# Acondicionamiento_de_la_se_al.net
KiCad netlist of a schematic drawn in Altium Designer
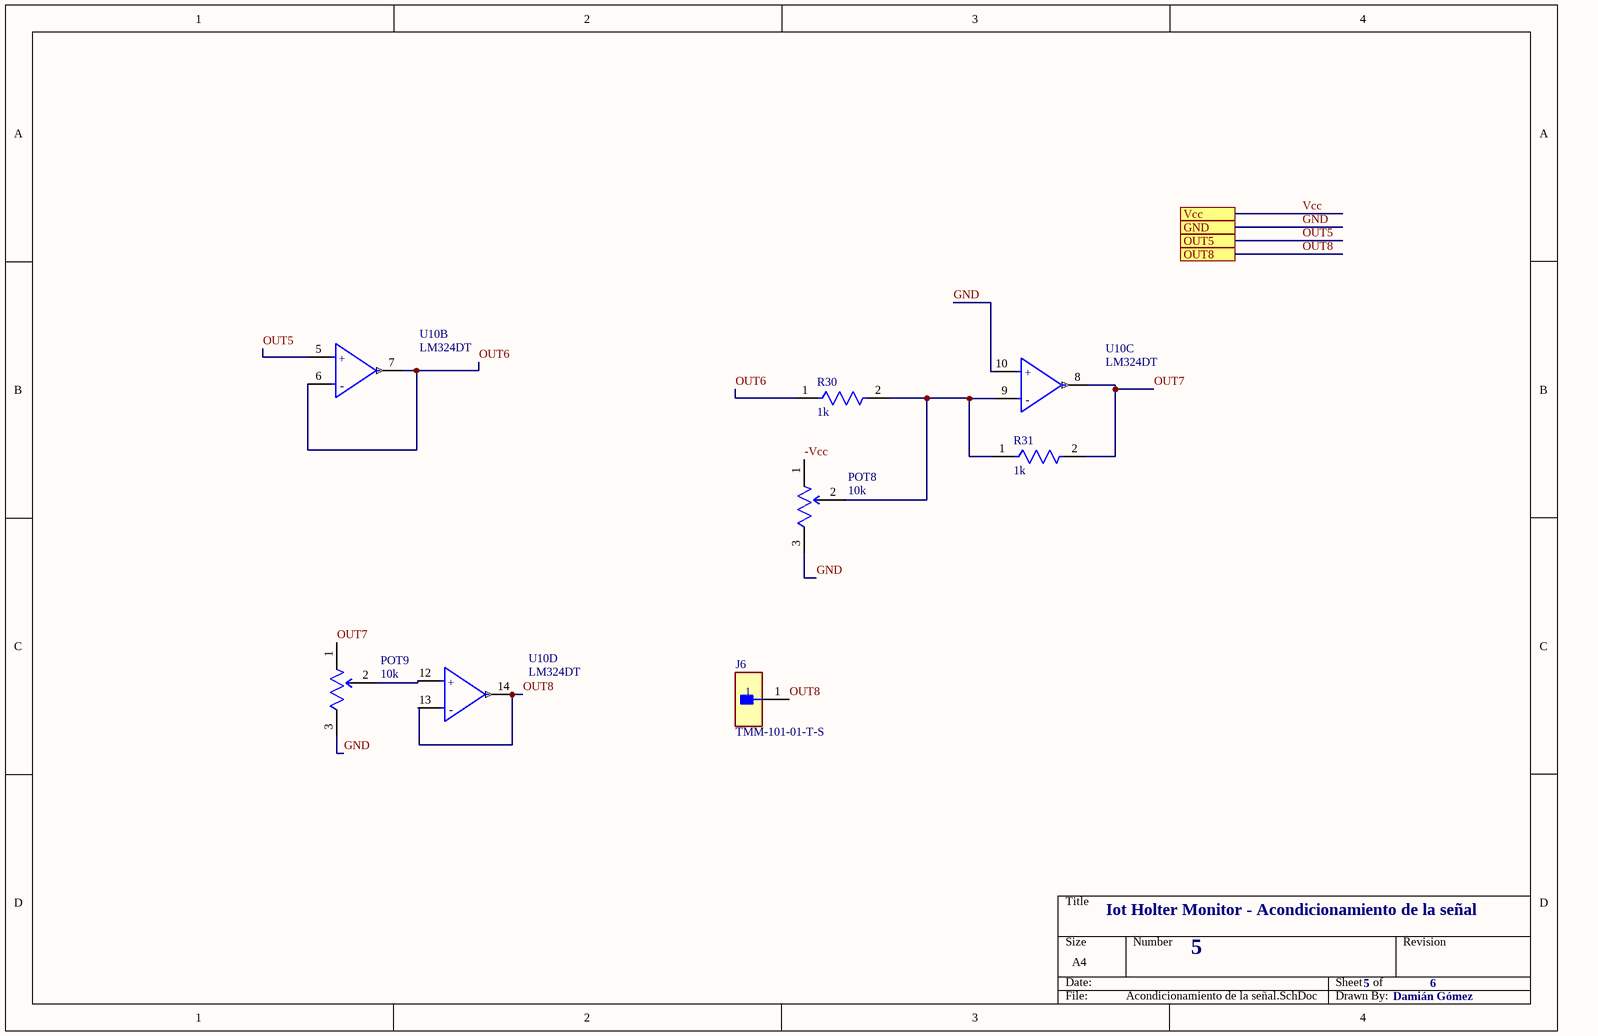
[diagram p0: Acondicionamiento de la señal.SchDoc]

(export (version "E")
  (design (tool "Eeschema 10.0.6"))
  (components
    (comp (ref "J6")
      (value "TMM-101-01-T-S")
      (footprint "FP-TMM-101-01-T-S-MFG")
      (description "CONN HEADER VERT 1POS")
      (libsource (lib "Altium Content Vault") (part "dd45045ce8184df9e99e12baf3f412c"))
    )
    (comp (ref "POT8")
      (value "10k")
      (footprint "FP-3296W-MFG")
      (description "TRIMMER 10K OHM 0.5W PC PIN TOP")
      (fields (field (name "TOLERANCE") "10%"))
      (libsource (lib "Altium Content Vault") (part "194907ebf2981c0cdd5d9631a0af656"))
    )
    (comp (ref "POT9")
      (value "10k")
      (footprint "FP-3296W-MFG")
      (description "TRIMMER 10K OHM 0.5W PC PIN TOP")
      (fields (field (name "TOLERANCE") "10%"))
      (libsource (lib "Altium Content Vault") (part "194907ebf2981c0cdd5d9631a0af656"))
    )
    (comp (ref "R30")
      (value "1k")
      (footprint "FP-RC3216-MFG")
      (description "Res Thick Film 1206 1kΩ 5% 0.25W ±100ppm/°C Molded SMD T/R")
      (fields (field (name "TOLERANCE") "5%"))
      (libsource (lib "Altium Content Vault") (part "1029c3af85768c4190bb7ad29bc67b5"))
    )
    (comp (ref "R31")
      (value "1k")
      (footprint "FP-RC3216-MFG")
      (description "Res Thick Film 1206 1kΩ 5% 0.25W ±100ppm/°C Molded SMD T/R")
      (fields (field (name "TOLERANCE") "5%"))
      (libsource (lib "Altium Content Vault") (part "1029c3af85768c4190bb7ad29bc67b5"))
    )
    (comp (ref "U10")
      (value "LM324DT")
      (footprint "FP-SO-14-MFG")
      (description "IC OPAMP GP 4 CIRCUIT 14SO")
      (fields
        (field (name "OCTOPART") "https://octopart.com/lm324dt-stmicroelectronics-39579146")
        (field (name "MANUFACTURER") "STMicroelectronics")
      )
      (libsource (lib "Altium Content Vault") (part "a065ef67e5aa9ef3942d43d6008d043"))
    )
  )
  (nets
    (net (code "1") (name "/-Vcc") (class "Default")
      (node (ref "POT8") (pin "1") (pinfunction "CCW_1") (pintype "passive"))
    )
    (net (code "2") (name "/GND") (class "Default")
      (node (ref "POT8") (pin "3") (pinfunction "CW_3") (pintype "passive"))
      (node (ref "POT9") (pin "3") (pinfunction "CW_3") (pintype "passive"))
      (node (ref "U10") (pin "10") (pinfunction "Non-Inverting_Input_3_10") (pintype "tri_state"))
    )
    (net (code "3") (name "/OUT5") (class "Default")
      (node (ref "U10") (pin "5") (pinfunction "Non-Inverting_Input_2_5") (pintype "passive"))
    )
    (net (code "4") (name "/OUT6") (class "Default")
      (node (ref "R30") (pin "1") (pinfunction "1_1") (pintype "passive"))
      (node (ref "U10") (pin "6") (pinfunction "Inverting_Input_2_6") (pintype "passive"))
      (node (ref "U10") (pin "7") (pinfunction "Output_2_7") (pintype "output"))
    )
    (net (code "5") (name "/OUT7") (class "Default")
      (node (ref "POT9") (pin "1") (pinfunction "CCW_1") (pintype "passive"))
      (node (ref "R31") (pin "2") (pinfunction "2_2") (pintype "passive"))
      (node (ref "U10") (pin "8") (pinfunction "Output_3_8") (pintype "output"))
    )
    (net (code "6") (name "/OUT8") (class "Default")
      (node (ref "J6") (pin "1") (pinfunction "1_1") (pintype "passive"))
      (node (ref "U10") (pin "13") (pinfunction "Inverting_Input_4_13") (pintype "tri_state"))
      (node (ref "U10") (pin "14") (pinfunction "Output_4_14") (pintype "output"))
    )
    (net (code "8") (name "Net-(POT8-WIPER)") (class "Default")
      (node (ref "POT8") (pin "2") (pinfunction "WIPER_2") (pintype "passive"))
      (node (ref "R30") (pin "2") (pinfunction "2_2") (pintype "passive"))
      (node (ref "R31") (pin "1") (pinfunction "1_1") (pintype "passive"))
      (node (ref "U10") (pin "9") (pinfunction "Inverting_Input_3_9") (pintype "tri_state"))
    )
    (net (code "9") (name "Net-(POT9-WIPER)") (class "Default")
      (node (ref "POT9") (pin "2") (pinfunction "WIPER_2") (pintype "passive"))
      (node (ref "U10") (pin "12") (pinfunction "Non-Inverting_Input_4_12") (pintype "tri_state"))
    )
  )
)
